# PWM.net
KiCad netlist of a schematic drawn in Altium Designer
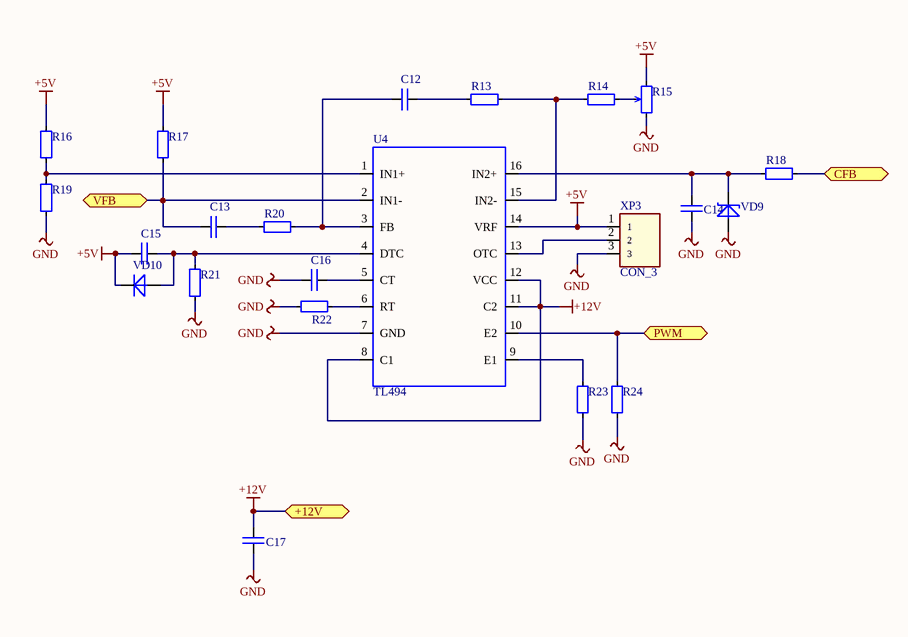
[diagram p0: PWM.SchDoc]

(export (version "E")
  (design (tool "Eeschema 10.0.6"))
  (components
    (comp (ref "C12")
      (value "~")
      (footprint "DISCRETE:SMD_0805")
      (description "None polar capacitor")
      (libsource (lib "DISCRETE") (part "C_NONE_POLAR"))
    )
    (comp (ref "C13")
      (value "~")
      (footprint "DISCRETE:SMD_0805")
      (description "None polar capacitor")
      (libsource (lib "DISCRETE") (part "C_NONE_POLAR"))
    )
    (comp (ref "C14")
      (value "~")
      (footprint "DISCRETE:SMD_0805")
      (description "None polar capacitor")
      (libsource (lib "DISCRETE") (part "C_NONE_POLAR"))
    )
    (comp (ref "C15")
      (value "~")
      (footprint "DISCRETE:SMD_1206")
      (description "None polar capacitor")
      (libsource (lib "DISCRETE") (part "C_NONE_POLAR"))
    )
    (comp (ref "C16")
      (value "~")
      (footprint "DISCRETE:SMD_0805")
      (description "None polar capacitor")
      (libsource (lib "DISCRETE") (part "C_NONE_POLAR"))
    )
    (comp (ref "C17")
      (value "~")
      (footprint "DISCRETE:SMD_0805")
      (description "None polar capacitor")
      (libsource (lib "DISCRETE") (part "C_NONE_POLAR"))
    )
    (comp (ref "R13")
      (value "~")
      (footprint "DISCRETE:SMD_0805")
      (description "Resistor")
      (libsource (lib "") (part "RES_3"))
    )
    (comp (ref "R14")
      (value "~")
      (footprint "DISCRETE:SMD_0805")
      (description "Resistor")
      (libsource (lib "") (part "RES_3"))
    )
    (comp (ref "R15")
      (value "~")
      (footprint "Connectors:HEAD-1/3/2.54")
      (description "Agjustable resistor")
      (libsource (lib "DISCRETE") (part "RES_ADJ"))
    )
    (comp (ref "R16")
      (value "~")
      (footprint "DISCRETE:SMD_0805")
      (description "Resistor")
      (libsource (lib "") (part "RES_1"))
    )
    (comp (ref "R17")
      (value "~")
      (footprint "DISCRETE:SMD_0805")
      (description "Resistor")
      (libsource (lib "") (part "RES_1"))
    )
    (comp (ref "R18")
      (value "~")
      (footprint "DISCRETE:SMD_0805")
      (description "Resistor")
      (libsource (lib "") (part "RES_2"))
    )
    (comp (ref "R19")
      (value "~")
      (footprint "DISCRETE:SMD_0805")
      (description "Resistor")
      (libsource (lib "") (part "RES_1"))
    )
    (comp (ref "R20")
      (value "~")
      (footprint "DISCRETE:SMD_0805")
      (description "Resistor")
      (libsource (lib "") (part "RES_3"))
    )
    (comp (ref "R21")
      (value "~")
      (footprint "DISCRETE:SMD_0805")
      (description "Resistor")
      (libsource (lib "DISCRETE") (part "RES"))
    )
    (comp (ref "R22")
      (value "~")
      (footprint "DISCRETE:SMD_0805")
      (description "Resistor")
      (libsource (lib "") (part "RES_3"))
    )
    (comp (ref "R23")
      (value "~")
      (footprint "DISCRETE:SMD_0805")
      (description "Resistor")
      (libsource (lib "DISCRETE") (part "RES"))
    )
    (comp (ref "R24")
      (value "~")
      (footprint "DISCRETE:SMD_0805")
      (description "Resistor")
      (libsource (lib "DISCRETE") (part "RES"))
    )
    (comp (ref "U4")
      (value "TL494")
      (footprint "ICs:SOIC-16")
      (description "PWM controller")
      (libsource (lib "ICs") (part "TL494"))
    )
    (comp (ref "VD9")
      (value "~")
      (footprint "DISCRETE:SOD-123")
      (description "Zener diode")
      (libsource (lib "DISCRETE") (part "ZENER"))
    )
    (comp (ref "VD10")
      (value "~")
      (footprint "DISCRETE:DIO-MELF_SOD-80")
      (description "Diode")
      (libsource (lib "DISCRETE") (part "DIODE"))
    )
    (comp (ref "XP3")
      (value "CON_3")
      (footprint "HEAD-1/3/2.54")
      (libsource (lib "Connectors") (part "CON_3"))
    )
  )
  (nets
    (net (code "1") (name "+5V") (class "Default")
      (node (ref "C15") (pin "2") (pintype "passive"))
      (node (ref "R15") (pin "2") (pintype "passive"))
      (node (ref "R16") (pin "2") (pintype "passive"))
      (node (ref "R17") (pin "2") (pintype "passive"))
      (node (ref "U4") (pin "14") (pinfunction "VRF_14") (pintype "passive"))
      (node (ref "VD10") (pin "1") (pinfunction "C_1") (pintype "passive"))
      (node (ref "XP3") (pin "1") (pinfunction "1_1") (pintype "passive"))
    )
    (net (code "2") (name "+12V") (class "Default")
      (node (ref "C17") (pin "1") (pintype "passive"))
      (node (ref "U4") (pin "11") (pinfunction "C2_11") (pintype "passive"))
      (node (ref "U4") (pin "12") (pinfunction "VCC_12") (pintype "passive"))
      (node (ref "U4") (pin "8") (pinfunction "C1_8") (pintype "passive"))
    )
    (net (code "3") (name "/CFB") (class "Default") (node (ref "R18") (pin "2") (pintype "passive")))
    (net (code "4") (name "/PWM") (class "Default")
      (node (ref "R24") (pin "1") (pintype "passive"))
      (node (ref "U4") (pin "10") (pinfunction "E2_10") (pintype "passive"))
    )
    (net (code "5") (name "/VFB") (class "Default")
      (node (ref "C13") (pin "2") (pintype "passive"))
      (node (ref "R17") (pin "1") (pintype "passive"))
      (node (ref "U4") (pin "2") (pinfunction "IN1-_2") (pintype "passive"))
    )
    (net (code "6") (name "GND") (class "Default")
      (node (ref "C14") (pin "1") (pintype "passive"))
      (node (ref "C16") (pin "2") (pintype "passive"))
      (node (ref "C17") (pin "2") (pintype "passive"))
      (node (ref "R15") (pin "1") (pintype "passive"))
      (node (ref "R19") (pin "1") (pintype "passive"))
      (node (ref "R21") (pin "2") (pintype "passive"))
      (node (ref "R22") (pin "2") (pintype "passive"))
      (node (ref "R23") (pin "2") (pintype "passive"))
      (node (ref "R24") (pin "2") (pintype "passive"))
      (node (ref "U4") (pin "7") (pinfunction "GND_7") (pintype "passive"))
      (node (ref "VD9") (pin "2") (pinfunction "A_2") (pintype "passive"))
      (node (ref "XP3") (pin "3") (pinfunction "3_3") (pintype "passive"))
    )
    (net (code "7") (name "Net-(C12-Pad1)") (class "Default")
      (node (ref "C12") (pin "1") (pintype "passive"))
      (node (ref "R13") (pin "2") (pintype "passive"))
    )
    (net (code "8") (name "Net-(C13-Pad1)") (class "Default")
      (node (ref "C13") (pin "1") (pintype "passive"))
      (node (ref "R20") (pin "2") (pintype "passive"))
    )
    (net (code "9") (name "Net-(R14-Pad1)") (class "Default")
      (node (ref "R14") (pin "1") (pintype "passive"))
      (node (ref "R15") (pin "3") (pintype "passive"))
    )
    (net (code "10") (name "Net-(U4-CT)") (class "Default")
      (node (ref "C16") (pin "1") (pintype "passive"))
      (node (ref "U4") (pin "5") (pinfunction "CT_5") (pintype "passive"))
    )
    (net (code "11") (name "Net-(U4-DTC)") (class "Default")
      (node (ref "C15") (pin "1") (pintype "passive"))
      (node (ref "R21") (pin "1") (pintype "passive"))
      (node (ref "U4") (pin "4") (pinfunction "DTC_4") (pintype "passive"))
      (node (ref "VD10") (pin "2") (pinfunction "A_2") (pintype "passive"))
    )
    (net (code "12") (name "Net-(U4-E1)") (class "Default")
      (node (ref "R23") (pin "1") (pintype "passive"))
      (node (ref "U4") (pin "9") (pinfunction "E1_9") (pintype "passive"))
    )
    (net (code "13") (name "Net-(U4-FB)") (class "Default")
      (node (ref "C12") (pin "2") (pintype "passive"))
      (node (ref "R20") (pin "1") (pintype "passive"))
      (node (ref "U4") (pin "3") (pinfunction "FB_3") (pintype "passive"))
    )
    (net (code "14") (name "Net-(U4-IN1+)") (class "Default")
      (node (ref "R16") (pin "1") (pintype "passive"))
      (node (ref "R19") (pin "2") (pintype "passive"))
      (node (ref "U4") (pin "1") (pinfunction "IN1+_1") (pintype "passive"))
    )
    (net (code "15") (name "Net-(U4-IN2+)") (class "Default")
      (node (ref "C14") (pin "2") (pintype "passive"))
      (node (ref "R18") (pin "1") (pintype "passive"))
      (node (ref "U4") (pin "16") (pinfunction "IN2+_16") (pintype "passive"))
      (node (ref "VD9") (pin "1") (pinfunction "C_1") (pintype "passive"))
    )
    (net (code "16") (name "Net-(U4-IN2-)") (class "Default")
      (node (ref "R13") (pin "1") (pintype "passive"))
      (node (ref "R14") (pin "2") (pintype "passive"))
      (node (ref "U4") (pin "15") (pinfunction "IN2-_15") (pintype "passive"))
    )
    (net (code "17") (name "Net-(U4-OTC)") (class "Default")
      (node (ref "U4") (pin "13") (pinfunction "OTC_13") (pintype "passive"))
      (node (ref "XP3") (pin "2") (pinfunction "2_2") (pintype "passive"))
    )
    (net (code "18") (name "Net-(U4-RT)") (class "Default")
      (node (ref "R22") (pin "1") (pintype "passive"))
      (node (ref "U4") (pin "6") (pinfunction "RT_6") (pintype "passive"))
    )
  )
)
